# power.net
KiCad netlist of a schematic drawn in Altium Designer
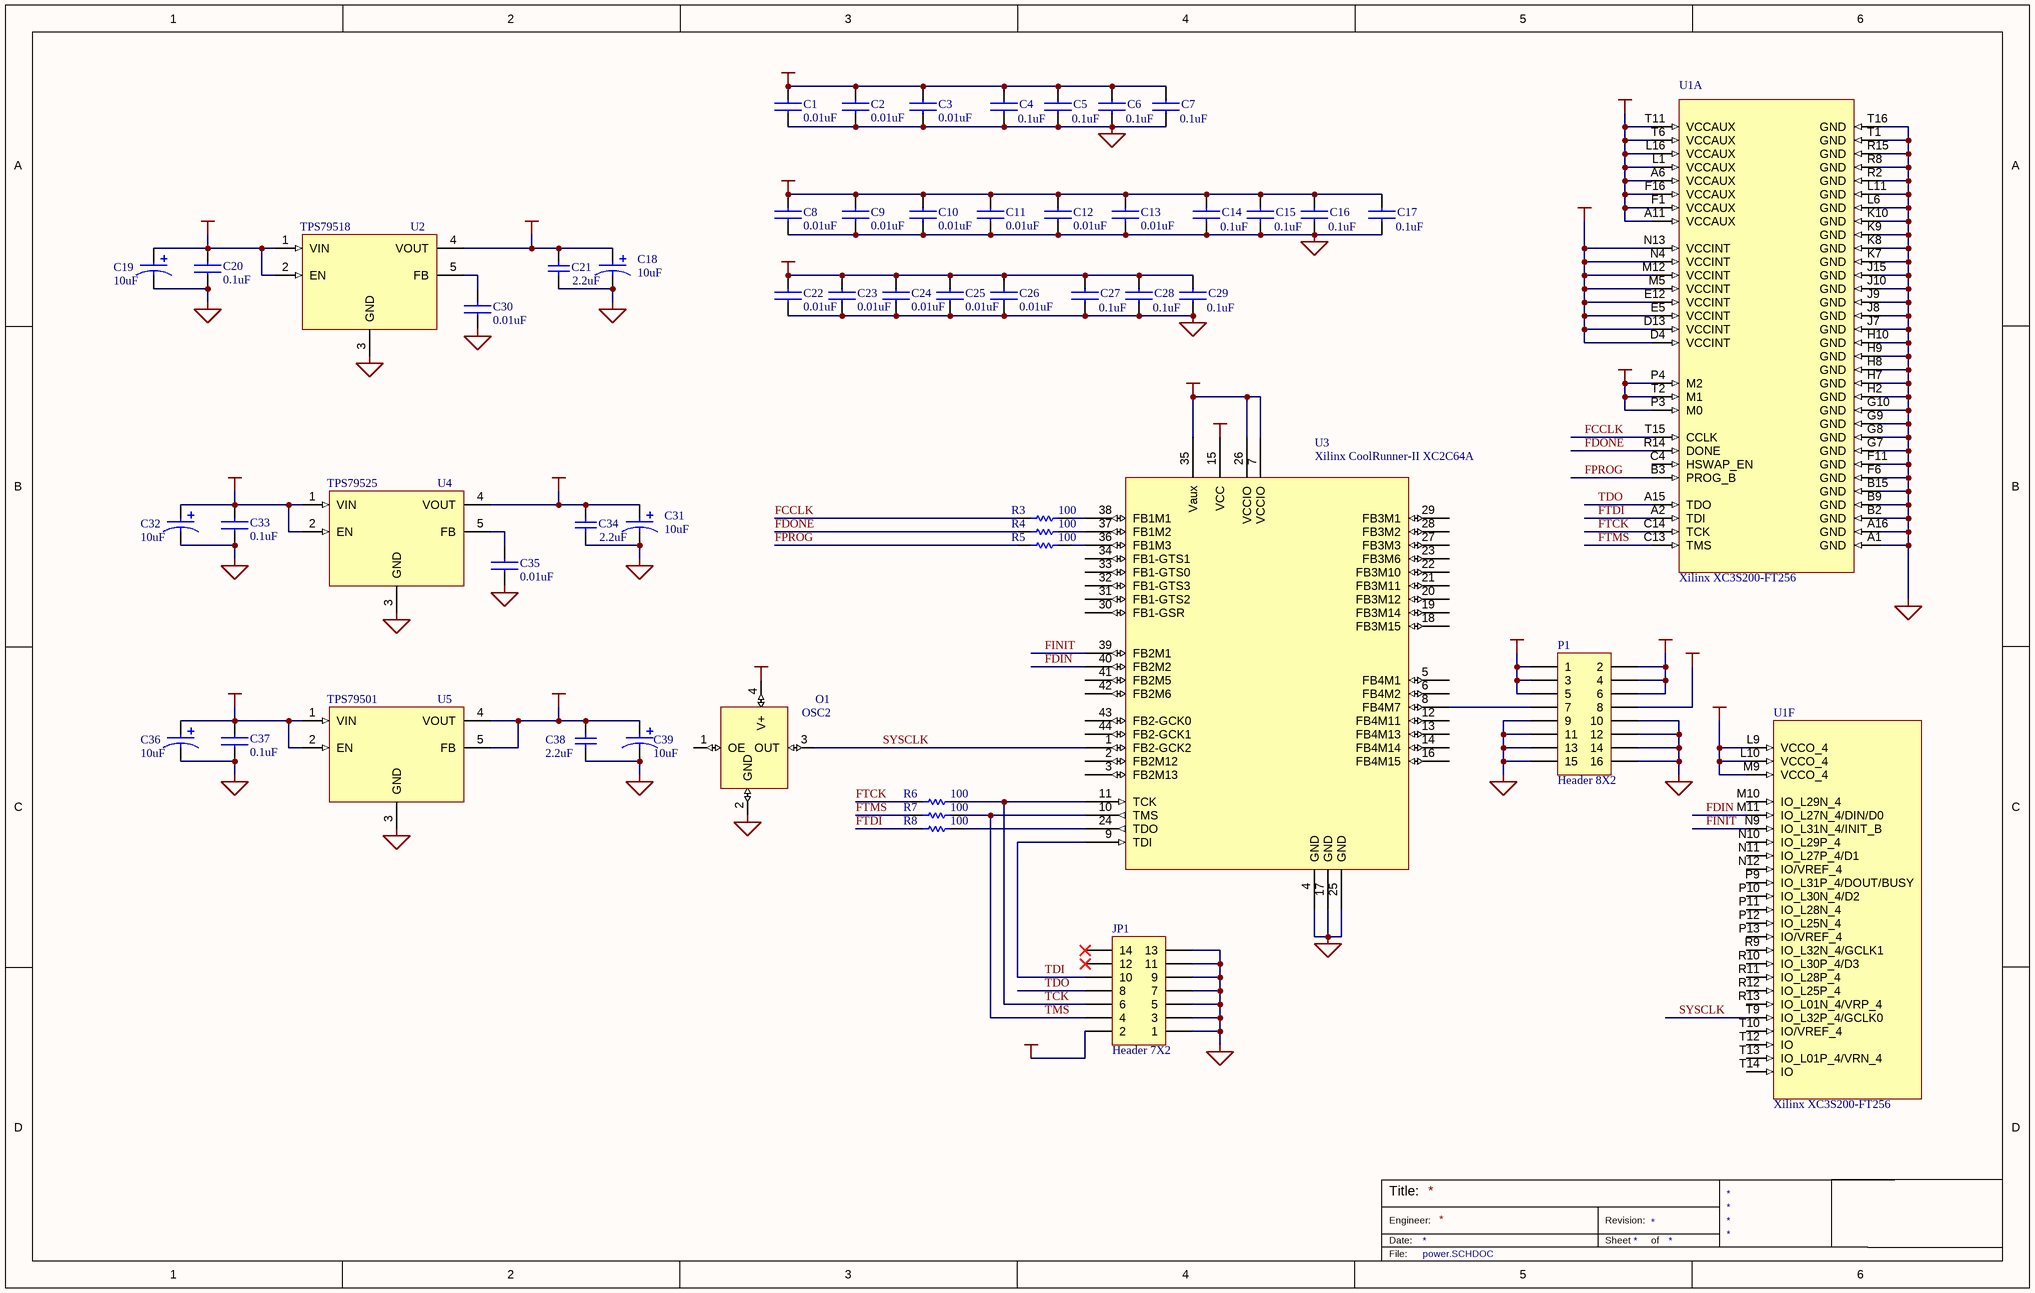
[diagram p0: power.SCHDOC]

(export (version "E")
  (design (tool "Eeschema 10.0.6"))
  (components
    (comp (ref "C1")
      (value "0.01uF")
      (footprint "0402")
      (description "Standard Capacitor")
      (fields (field (name "Comment") "CAPACITOR"))
      (libsource (lib "parts") (part "CAPACITOR"))
    )
    (comp (ref "C2")
      (value "0.01uF")
      (footprint "0402")
      (description "Standard Capacitor")
      (fields (field (name "Comment") "CAPACITOR"))
      (libsource (lib "parts") (part "CAPACITOR"))
    )
    (comp (ref "C3")
      (value "0.01uF")
      (footprint "0402")
      (description "Standard Capacitor")
      (fields (field (name "Comment") "CAPACITOR"))
      (libsource (lib "parts") (part "CAPACITOR"))
    )
    (comp (ref "C4")
      (value "0.1uF")
      (footprint "0603")
      (description "Standard Capacitor")
      (fields (field (name "Comment") "CAPACITOR"))
      (libsource (lib "parts") (part "CAPACITOR"))
    )
    (comp (ref "C5")
      (value "0.1uF")
      (footprint "0603")
      (description "Standard Capacitor")
      (fields (field (name "Comment") "CAPACITOR"))
      (libsource (lib "parts") (part "CAPACITOR"))
    )
    (comp (ref "C6")
      (value "0.1uF")
      (footprint "0603")
      (description "Standard Capacitor")
      (fields (field (name "Comment") "CAPACITOR"))
      (libsource (lib "parts") (part "CAPACITOR"))
    )
    (comp (ref "C7")
      (value "0.1uF")
      (footprint "0603")
      (description "Standard Capacitor")
      (fields (field (name "Comment") "CAPACITOR"))
      (libsource (lib "parts") (part "CAPACITOR"))
    )
    (comp (ref "C8")
      (value "0.01uF")
      (footprint "0402")
      (description "Standard Capacitor")
      (fields (field (name "Comment") "CAPACITOR"))
      (libsource (lib "parts") (part "CAPACITOR"))
    )
    (comp (ref "C9")
      (value "0.01uF")
      (footprint "0402")
      (description "Standard Capacitor")
      (fields (field (name "Comment") "CAPACITOR"))
      (libsource (lib "parts") (part "CAPACITOR"))
    )
    (comp (ref "C10")
      (value "0.01uF")
      (footprint "0402")
      (description "Standard Capacitor")
      (fields (field (name "Comment") "CAPACITOR"))
      (libsource (lib "parts") (part "CAPACITOR"))
    )
    (comp (ref "C11")
      (value "0.01uF")
      (footprint "0402")
      (description "Standard Capacitor")
      (fields (field (name "Comment") "CAPACITOR"))
      (libsource (lib "parts") (part "CAPACITOR"))
    )
    (comp (ref "C12")
      (value "0.01uF")
      (footprint "0402")
      (description "Standard Capacitor")
      (fields (field (name "Comment") "CAPACITOR"))
      (libsource (lib "parts") (part "CAPACITOR"))
    )
    (comp (ref "C13")
      (value "0.01uF")
      (footprint "0402")
      (description "Standard Capacitor")
      (fields (field (name "Comment") "CAPACITOR"))
      (libsource (lib "parts") (part "CAPACITOR"))
    )
    (comp (ref "C14")
      (value "0.1uF")
      (footprint "0603")
      (description "Standard Capacitor")
      (fields (field (name "Comment") "CAPACITOR"))
      (libsource (lib "parts") (part "CAPACITOR"))
    )
    (comp (ref "C15")
      (value "0.1uF")
      (footprint "0603")
      (description "Standard Capacitor")
      (fields (field (name "Comment") "CAPACITOR"))
      (libsource (lib "parts") (part "CAPACITOR"))
    )
    (comp (ref "C16")
      (value "0.1uF")
      (footprint "0603")
      (description "Standard Capacitor")
      (fields (field (name "Comment") "CAPACITOR"))
      (libsource (lib "parts") (part "CAPACITOR"))
    )
    (comp (ref "C17")
      (value "0.1uF")
      (footprint "0603")
      (description "Standard Capacitor")
      (fields (field (name "Comment") "CAPACITOR"))
      (libsource (lib "parts") (part "CAPACITOR"))
    )
    (comp (ref "C18")
      (value "10uF")
      (footprint "6032")
      (description "Standard Capacitor")
      (fields (field (name "Comment") "POLCAP2"))
      (libsource (lib "parts") (part "POLCAP2"))
    )
    (comp (ref "C19")
      (value "10uF")
      (footprint "6032")
      (description "Standard Capacitor")
      (fields (field (name "Comment") "POLCAP2"))
      (libsource (lib "parts") (part "POLCAP2"))
    )
    (comp (ref "C20")
      (value "0.1uF")
      (footprint "0603")
      (description "Standard Capacitor")
      (fields (field (name "Comment") "CAPACITOR"))
      (libsource (lib "parts") (part "CAPACITOR"))
    )
    (comp (ref "C21")
      (value "2.2uF")
      (footprint "1206")
      (description "Capacitor")
      (fields
        (field (name "MANUFACTURER") "Generic Components")
        (field (name "Comment") "Cap")
        (field (name "PUBLISHER") "Altium Limited")
      )
      (libsource (lib "Miscellaneous Devices") (part "Cap"))
    )
    (comp (ref "C22")
      (value "0.01uF")
      (footprint "0402")
      (description "Standard Capacitor")
      (fields (field (name "Comment") "CAPACITOR"))
      (libsource (lib "parts") (part "CAPACITOR"))
    )
    (comp (ref "C23")
      (value "0.01uF")
      (footprint "0402")
      (description "Standard Capacitor")
      (fields (field (name "Comment") "CAPACITOR"))
      (libsource (lib "parts") (part "CAPACITOR"))
    )
    (comp (ref "C24")
      (value "0.01uF")
      (footprint "0402")
      (description "Standard Capacitor")
      (fields (field (name "Comment") "CAPACITOR"))
      (libsource (lib "parts") (part "CAPACITOR"))
    )
    (comp (ref "C25")
      (value "0.01uF")
      (footprint "0402")
      (description "Standard Capacitor")
      (fields (field (name "Comment") "CAPACITOR"))
      (libsource (lib "parts") (part "CAPACITOR"))
    )
    (comp (ref "C26")
      (value "0.01uF")
      (footprint "0402")
      (description "Standard Capacitor")
      (fields (field (name "Comment") "CAPACITOR"))
      (libsource (lib "parts") (part "CAPACITOR"))
    )
    (comp (ref "C27")
      (value "0.1uF")
      (footprint "0603")
      (description "Standard Capacitor")
      (fields (field (name "Comment") "CAPACITOR"))
      (libsource (lib "parts") (part "CAPACITOR"))
    )
    (comp (ref "C28")
      (value "0.1uF")
      (footprint "0603")
      (description "Standard Capacitor")
      (fields (field (name "Comment") "CAPACITOR"))
      (libsource (lib "parts") (part "CAPACITOR"))
    )
    (comp (ref "C29")
      (value "0.1uF")
      (footprint "0603")
      (description "Standard Capacitor")
      (fields (field (name "Comment") "CAPACITOR"))
      (libsource (lib "parts") (part "CAPACITOR"))
    )
    (comp (ref "C30")
      (value "0.01uF")
      (footprint "0402")
      (description "Standard Capacitor")
      (fields (field (name "Comment") "CAPACITOR"))
      (libsource (lib "parts") (part "CAPACITOR"))
    )
    (comp (ref "C31")
      (value "10uF")
      (footprint "6032")
      (description "Standard Capacitor")
      (fields (field (name "Comment") "POLCAP2"))
      (libsource (lib "parts") (part "POLCAP2"))
    )
    (comp (ref "C32")
      (value "10uF")
      (footprint "6032")
      (description "Standard Capacitor")
      (fields (field (name "Comment") "POLCAP2"))
      (libsource (lib "parts") (part "POLCAP2"))
    )
    (comp (ref "C33")
      (value "0.1uF")
      (footprint "0603")
      (description "Standard Capacitor")
      (fields (field (name "Comment") "CAPACITOR"))
      (libsource (lib "parts") (part "CAPACITOR"))
    )
    (comp (ref "C34")
      (value "2.2uF")
      (footprint "1206")
      (description "Capacitor")
      (fields
        (field (name "MANUFACTURER") "Generic Components")
        (field (name "Comment") "Cap")
        (field (name "PUBLISHER") "Altium Limited")
      )
      (libsource (lib "Miscellaneous Devices") (part "Cap"))
    )
    (comp (ref "C35")
      (value "0.01uF")
      (footprint "0402")
      (description "Standard Capacitor")
      (fields (field (name "Comment") "CAPACITOR"))
      (libsource (lib "parts") (part "CAPACITOR"))
    )
    (comp (ref "C36")
      (value "10uF")
      (footprint "6032")
      (description "Standard Capacitor")
      (fields (field (name "Comment") "POLCAP2"))
      (libsource (lib "parts") (part "POLCAP2"))
    )
    (comp (ref "C37")
      (value "0.1uF")
      (footprint "0603")
      (description "Standard Capacitor")
      (fields (field (name "Comment") "CAPACITOR"))
      (libsource (lib "parts") (part "CAPACITOR"))
    )
    (comp (ref "C38")
      (value "2.2uF")
      (footprint "1206")
      (description "Capacitor")
      (fields
        (field (name "MANUFACTURER") "Generic Components")
        (field (name "Comment") "Cap")
        (field (name "PUBLISHER") "Altium Limited")
      )
      (libsource (lib "Miscellaneous Devices") (part "Cap"))
    )
    (comp (ref "C39")
      (value "10uF")
      (footprint "6032")
      (description "Standard Capacitor")
      (fields (field (name "Comment") "POLCAP2"))
      (libsource (lib "parts") (part "POLCAP2"))
    )
    (comp (ref "JP1")
      (value "Header 7X2")
      (footprint "SMT 2x7 2mm HDR")
      (description "Header, 7-Pin, Dual row")
      (fields (field (name "MANUFACTURER") "Generic Components") (field (name "PUBLISHER") "Altium Limited"))
      (libsource (lib "Miscellaneous Connectors") (part "Header 7X2"))
    )
    (comp (ref "O1")
      (value "OSC2")
      (footprint "ECS-3953M")
      (description "ECS SMD Oscillator, ECS-3953M")
      (libsource (lib "parts") (part "OSC2"))
    )
    (comp (ref "P1")
      (value "Header 8X2")
      (footprint "MOLEX 15-91-2160")
      (description "Header, 8-Pin, Dual row")
      (fields (field (name "PUBLISHER") "Altium Limited"))
      (libsource (lib "Miscellaneous Connectors") (part "Header 8X2"))
    )
    (comp (ref "R3")
      (value "100")
      (footprint "CC1608-0603")
      (description "Resistor")
      (fields
        (field (name "MANUFACTURER") "Generic Components")
        (field (name "TOLERANCE") "1%")
        (field (name "PUBLISHER") "Altium Limited")
      )
      (libsource (lib "Miscellaneous Devices") (part "Res1"))
    )
    (comp (ref "R4")
      (value "100")
      (footprint "CC1608-0603")
      (description "Resistor")
      (fields
        (field (name "MANUFACTURER") "Generic Components")
        (field (name "TOLERANCE") "1%")
        (field (name "PUBLISHER") "Altium Limited")
      )
      (libsource (lib "Miscellaneous Devices") (part "Res1"))
    )
    (comp (ref "R5")
      (value "100")
      (footprint "CC1608-0603")
      (description "Resistor")
      (fields
        (field (name "MANUFACTURER") "Generic Components")
        (field (name "TOLERANCE") "1%")
        (field (name "PUBLISHER") "Altium Limited")
      )
      (libsource (lib "Miscellaneous Devices") (part "Res1"))
    )
    (comp (ref "R6")
      (value "100")
      (footprint "CC1608-0603")
      (description "Resistor")
      (fields
        (field (name "MANUFACTURER") "Generic Components")
        (field (name "TOLERANCE") "1%")
        (field (name "PUBLISHER") "Altium Limited")
      )
      (libsource (lib "Miscellaneous Devices") (part "Res1"))
    )
    (comp (ref "R7")
      (value "100")
      (footprint "CC1608-0603")
      (description "Resistor")
      (fields
        (field (name "MANUFACTURER") "Generic Components")
        (field (name "TOLERANCE") "1%")
        (field (name "PUBLISHER") "Altium Limited")
      )
      (libsource (lib "Miscellaneous Devices") (part "Res1"))
    )
    (comp (ref "R8")
      (value "100")
      (footprint "CC1608-0603")
      (description "Resistor")
      (fields
        (field (name "MANUFACTURER") "Generic Components")
        (field (name "TOLERANCE") "1%")
        (field (name "PUBLISHER") "Altium Limited")
      )
      (libsource (lib "Miscellaneous Devices") (part "Res1"))
    )
    (comp (ref "U1")
      (value "Xilinx XC3S200-FT256")
      (footprint "Xilinx FT256 BGA")
      (description "Xilinx Spartan-3 FPGA")
      (libsource (lib "parts") (part "XC3S200-FT256"))
    )
    (comp (ref "U2")
      (value "TPS79518")
      (footprint "SOT223-5/Simple")
      (description "TI Ultra-low-noise LDO")
      (libsource (lib "parts") (part "TPS795XX"))
    )
    (comp (ref "U3")
      (value "Xilinx CoolRunner-II XC2C64A")
      (footprint "QFP10x10-G44/G10N")
      (libsource (lib "parts") (part "XC2C64A-5VQ44C"))
    )
    (comp (ref "U4")
      (value "TPS79525")
      (footprint "SOT223-5/Simple")
      (description "TI Ultra-low-noise LDO")
      (libsource (lib "parts") (part "TPS795XX"))
    )
    (comp (ref "U5")
      (value "TPS79501")
      (footprint "SOT223-5/Simple")
      (description "TI Ultra-low-noise LDO")
      (libsource (lib "parts") (part "TPS795XX"))
    )
  )
  (nets
    (net (code "1") (name "+1.2VCC") (class "Default")
      (node (ref "C1") (pin "1") (pintype "passive"))
      (node (ref "C2") (pin "1") (pintype "passive"))
      (node (ref "C3") (pin "1") (pintype "passive"))
      (node (ref "C38") (pin "2") (pinfunction "2_2") (pintype "passive"))
      (node (ref "C39") (pin "1") (pintype "passive"))
      (node (ref "C4") (pin "1") (pintype "passive"))
      (node (ref "C5") (pin "1") (pintype "passive"))
      (node (ref "C6") (pin "1") (pintype "passive"))
      (node (ref "C7") (pin "1") (pintype "passive"))
      (node (ref "U1") (pin "D13") (pinfunction "VCCINT_D13") (pintype "input"))
      (node (ref "U1") (pin "D4") (pinfunction "VCCINT_D4") (pintype "input"))
      (node (ref "U1") (pin "E12") (pinfunction "VCCINT_E12") (pintype "input"))
      (node (ref "U1") (pin "E5") (pinfunction "VCCINT_E5") (pintype "input"))
      (node (ref "U1") (pin "M12") (pinfunction "VCCINT_M12") (pintype "input"))
      (node (ref "U1") (pin "M5") (pinfunction "VCCINT_M5") (pintype "input"))
      (node (ref "U1") (pin "N13") (pinfunction "VCCINT_N13") (pintype "input"))
      (node (ref "U1") (pin "N4") (pinfunction "VCCINT_N4") (pintype "input"))
      (node (ref "U5") (pin "4") (pinfunction "VOUT_4") (pintype "power_in"))
      (node (ref "U5") (pin "5") (pinfunction "FB_5") (pintype "passive"))
    )
    (net (code "2") (name "+1.8VCC") (class "Default")
      (node (ref "C18") (pin "1") (pintype "passive"))
      (node (ref "C21") (pin "2") (pinfunction "2_2") (pintype "passive"))
      (node (ref "U2") (pin "4") (pinfunction "VOUT_4") (pintype "power_in"))
      (node (ref "U3") (pin "15") (pinfunction "VCC_15") (pintype "power_in"))
    )
    (net (code "3") (name "+2.5VCC") (class "Default")
      (node (ref "C10") (pin "1") (pintype "passive"))
      (node (ref "C11") (pin "1") (pintype "passive"))
      (node (ref "C12") (pin "1") (pintype "passive"))
      (node (ref "C13") (pin "1") (pintype "passive"))
      (node (ref "C14") (pin "1") (pintype "passive"))
      (node (ref "C15") (pin "1") (pintype "passive"))
      (node (ref "C16") (pin "1") (pintype "passive"))
      (node (ref "C17") (pin "1") (pintype "passive"))
      (node (ref "C31") (pin "1") (pintype "passive"))
      (node (ref "C34") (pin "2") (pinfunction "2_2") (pintype "passive"))
      (node (ref "C8") (pin "1") (pintype "passive"))
      (node (ref "C9") (pin "1") (pintype "passive"))
      (node (ref "U1") (pin "A11") (pinfunction "VCCAUX_A11") (pintype "input"))
      (node (ref "U1") (pin "A6") (pinfunction "VCCAUX_A6") (pintype "input"))
      (node (ref "U1") (pin "F1") (pinfunction "VCCAUX_F1") (pintype "input"))
      (node (ref "U1") (pin "F16") (pinfunction "VCCAUX_F16") (pintype "input"))
      (node (ref "U1") (pin "L1") (pinfunction "VCCAUX_L1") (pintype "input"))
      (node (ref "U1") (pin "L16") (pinfunction "VCCAUX_L16") (pintype "input"))
      (node (ref "U1") (pin "T11") (pinfunction "VCCAUX_T11") (pintype "input"))
      (node (ref "U1") (pin "T6") (pinfunction "VCCAUX_T6") (pintype "input"))
      (node (ref "U4") (pin "4") (pinfunction "VOUT_4") (pintype "power_in"))
    )
    (net (code "4") (name "+5VCC") (class "Default")
      (node (ref "P1") (pin "2") (pinfunction "2_2") (pintype "passive"))
      (node (ref "P1") (pin "4") (pinfunction "4_4") (pintype "passive"))
      (node (ref "P1") (pin "6") (pinfunction "6_6") (pintype "passive"))
    )
    (net (code "5") (name "+12VCC") (class "Default")
      (node (ref "P1") (pin "8") (pinfunction "8_8") (pintype "passive"))
    )
    (net (code "6") (name "/FCCLK") (class "Default")
      (node (ref "R3") (pin "2") (pinfunction "2_2") (pintype "passive"))
      (node (ref "U1") (pin "T15") (pinfunction "CCLK_T15") (pintype "input"))
    )
    (net (code "7") (name "/FDIN") (class "Default")
      (node (ref "U1") (pin "M11") (pinfunction "IO_L27N_4/DIN/D0_M11") (pintype "input"))
      (node (ref "U3") (pin "40") (pinfunction "FB2M2_40") (pintype "bidirectional"))
    )
    (net (code "8") (name "/FDONE") (class "Default")
      (node (ref "R4") (pin "2") (pinfunction "2_2") (pintype "passive"))
      (node (ref "U1") (pin "R14") (pinfunction "DONE_R14") (pintype "input"))
    )
    (net (code "9") (name "/FINIT") (class "Default")
      (node (ref "U1") (pin "N9") (pinfunction "IO_L31N_4/INIT_B_N9") (pintype "input"))
      (node (ref "U3") (pin "39") (pinfunction "FB2M1_39") (pintype "bidirectional"))
    )
    (net (code "10") (name "/FPROG") (class "Default")
      (node (ref "R5") (pin "2") (pinfunction "2_2") (pintype "passive"))
      (node (ref "U1") (pin "B3") (pinfunction "PROG_B_B3") (pintype "input"))
    )
    (net (code "11") (name "/FTCK") (class "Default")
      (node (ref "R6") (pin "2") (pinfunction "2_2") (pintype "passive"))
      (node (ref "U1") (pin "C14") (pinfunction "TCK_C14") (pintype "input"))
    )
    (net (code "12") (name "/FTDI") (class "Default")
      (node (ref "R8") (pin "2") (pinfunction "2_2") (pintype "passive"))
      (node (ref "U1") (pin "A2") (pinfunction "TDI_A2") (pintype "input"))
    )
    (net (code "13") (name "/FTMS") (class "Default")
      (node (ref "R7") (pin "1") (pinfunction "1_1") (pintype "passive"))
      (node (ref "U1") (pin "C13") (pinfunction "TMS_C13") (pintype "input"))
    )
    (net (code "14") (name "/SYSCLK") (class "Default")
      (node (ref "O1") (pin "3") (pinfunction "OUT_3") (pintype "bidirectional"))
      (node (ref "U1") (pin "T9") (pinfunction "IO_L32P_4/GCLK0_T9") (pintype "input"))
      (node (ref "U3") (pin "1") (pinfunction "FB2-GCK2_1") (pintype "bidirectional"))
    )
    (net (code "15") (name "/TCK") (class "Default")
      (node (ref "JP1") (pin "6") (pinfunction "6_6") (pintype "passive"))
      (node (ref "R6") (pin "1") (pinfunction "1_1") (pintype "passive"))
      (node (ref "U3") (pin "11") (pinfunction "TCK_11") (pintype "input"))
    )
    (net (code "16") (name "/TDI") (class "Default")
      (node (ref "JP1") (pin "10") (pinfunction "10_10") (pintype "passive"))
      (node (ref "U3") (pin "9") (pinfunction "TDI_9") (pintype "input"))
    )
    (net (code "17") (name "/TDO") (class "Default")
      (node (ref "JP1") (pin "8") (pinfunction "8_8") (pintype "passive"))
      (node (ref "U1") (pin "A15") (pinfunction "TDO_A15") (pintype "input"))
    )
    (net (code "18") (name "/TMS") (class "Default")
      (node (ref "JP1") (pin "4") (pinfunction "4_4") (pintype "passive"))
      (node (ref "R7") (pin "2") (pinfunction "2_2") (pintype "passive"))
      (node (ref "U3") (pin "10") (pinfunction "TMS_10") (pintype "output"))
    )
    (net (code "19") (name "GND") (class "Default")
      (node (ref "C1") (pin "2") (pintype "passive"))
      (node (ref "C10") (pin "2") (pintype "passive"))
      (node (ref "C11") (pin "2") (pintype "passive"))
      (node (ref "C12") (pin "2") (pintype "passive"))
      (node (ref "C13") (pin "2") (pintype "passive"))
      (node (ref "C14") (pin "2") (pintype "passive"))
      (node (ref "C15") (pin "2") (pintype "passive"))
      (node (ref "C16") (pin "2") (pintype "passive"))
      (node (ref "C17") (pin "2") (pintype "passive"))
      (node (ref "C18") (pin "2") (pintype "passive"))
      (node (ref "C19") (pin "2") (pintype "passive"))
      (node (ref "C2") (pin "2") (pintype "passive"))
      (node (ref "C20") (pin "1") (pintype "passive"))
      (node (ref "C21") (pin "1") (pinfunction "1_1") (pintype "passive"))
      (node (ref "C22") (pin "2") (pintype "passive"))
      (node (ref "C23") (pin "2") (pintype "passive"))
      (node (ref "C24") (pin "2") (pintype "passive"))
      (node (ref "C25") (pin "2") (pintype "passive"))
      (node (ref "C26") (pin "2") (pintype "passive"))
      (node (ref "C27") (pin "2") (pintype "passive"))
      (node (ref "C28") (pin "2") (pintype "passive"))
      (node (ref "C29") (pin "2") (pintype "passive"))
      (node (ref "C3") (pin "2") (pintype "passive"))
      (node (ref "C30") (pin "1") (pintype "passive"))
      (node (ref "C31") (pin "2") (pintype "passive"))
      (node (ref "C32") (pin "2") (pintype "passive"))
      (node (ref "C33") (pin "1") (pintype "passive"))
      (node (ref "C34") (pin "1") (pinfunction "1_1") (pintype "passive"))
      (node (ref "C35") (pin "1") (pintype "passive"))
      (node (ref "C36") (pin "2") (pintype "passive"))
      (node (ref "C37") (pin "1") (pintype "passive"))
      (node (ref "C38") (pin "1") (pinfunction "1_1") (pintype "passive"))
      (node (ref "C39") (pin "2") (pintype "passive"))
      (node (ref "C4") (pin "2") (pintype "passive"))
      (node (ref "C5") (pin "2") (pintype "passive"))
      (node (ref "C6") (pin "2") (pintype "passive"))
      (node (ref "C7") (pin "2") (pintype "passive"))
      (node (ref "C8") (pin "2") (pintype "passive"))
      (node (ref "C9") (pin "2") (pintype "passive"))
      (node (ref "JP1") (pin "1") (pinfunction "1_1") (pintype "passive"))
      (node (ref "JP1") (pin "11") (pinfunction "11_11") (pintype "passive"))
      (node (ref "JP1") (pin "13") (pinfunction "13_13") (pintype "passive"))
      (node (ref "JP1") (pin "3") (pinfunction "3_3") (pintype "passive"))
      (node (ref "JP1") (pin "5") (pinfunction "5_5") (pintype "passive"))
      (node (ref "JP1") (pin "7") (pinfunction "7_7") (pintype "passive"))
      (node (ref "JP1") (pin "9") (pinfunction "9_9") (pintype "passive"))
      (node (ref "O1") (pin "2") (pinfunction "GND_2") (pintype "bidirectional"))
      (node (ref "P1") (pin "10") (pinfunction "10_10") (pintype "passive"))
      (node (ref "P1") (pin "11") (pinfunction "11_11") (pintype "passive"))
      (node (ref "P1") (pin "12") (pinfunction "12_12") (pintype "passive"))
      (node (ref "P1") (pin "13") (pinfunction "13_13") (pintype "passive"))
      (node (ref "P1") (pin "14") (pinfunction "14_14") (pintype "passive"))
      (node (ref "P1") (pin "15") (pinfunction "15_15") (pintype "passive"))
      (node (ref "P1") (pin "16") (pinfunction "16_16") (pintype "passive"))
      (node (ref "P1") (pin "9") (pinfunction "9_9") (pintype "passive"))
      (node (ref "U1") (pin "A1") (pinfunction "GND_A1") (pintype "input"))
      (node (ref "U1") (pin "A16") (pinfunction "GND_A16") (pintype "input"))
      (node (ref "U1") (pin "B15") (pinfunction "GND_B15") (pintype "input"))
      (node (ref "U1") (pin "B2") (pinfunction "GND_B2") (pintype "input"))
      (node (ref "U1") (pin "B9") (pinfunction "GND_B9") (pintype "input"))
      (node (ref "U1") (pin "F11") (pinfunction "GND_F11") (pintype "input"))
      (node (ref "U1") (pin "F6") (pinfunction "GND_F6") (pintype "input"))
      (node (ref "U1") (pin "G10") (pinfunction "GND_G10") (pintype "input"))
      (node (ref "U1") (pin "G7") (pinfunction "GND_G7") (pintype "input"))
      (node (ref "U1") (pin "G8") (pinfunction "GND_G8") (pintype "input"))
      (node (ref "U1") (pin "G9") (pinfunction "GND_G9") (pintype "input"))
      (node (ref "U1") (pin "H10") (pinfunction "GND_H10") (pintype "input"))
      (node (ref "U1") (pin "H2") (pinfunction "GND_H2") (pintype "input"))
      (node (ref "U1") (pin "H7") (pinfunction "GND_H7") (pintype "input"))
      (node (ref "U1") (pin "H8") (pinfunction "GND_H8") (pintype "input"))
      (node (ref "U1") (pin "H9") (pinfunction "GND_H9") (pintype "input"))
      (node (ref "U1") (pin "J10") (pinfunction "GND_J10") (pintype "input"))
      (node (ref "U1") (pin "J15") (pinfunction "GND_J15") (pintype "input"))
      (node (ref "U1") (pin "J7") (pinfunction "GND_J7") (pintype "input"))
      (node (ref "U1") (pin "J8") (pinfunction "GND_J8") (pintype "input"))
      (node (ref "U1") (pin "J9") (pinfunction "GND_J9") (pintype "input"))
      (node (ref "U1") (pin "K10") (pinfunction "GND_K10") (pintype "input"))
      (node (ref "U1") (pin "K7") (pinfunction "GND_K7") (pintype "input"))
      (node (ref "U1") (pin "K8") (pinfunction "GND_K8") (pintype "input"))
      (node (ref "U1") (pin "K9") (pinfunction "GND_K9") (pintype "input"))
      (node (ref "U1") (pin "L11") (pinfunction "GND_L11") (pintype "input"))
      (node (ref "U1") (pin "L6") (pinfunction "GND_L6") (pintype "input"))
      (node (ref "U1") (pin "R15") (pinfunction "GND_R15") (pintype "input"))
      (node (ref "U1") (pin "R2") (pinfunction "GND_R2") (pintype "input"))
      (node (ref "U1") (pin "R8") (pinfunction "GND_R8") (pintype "input"))
      (node (ref "U1") (pin "T1") (pinfunction "GND_T1") (pintype "input"))
      (node (ref "U1") (pin "T16") (pinfunction "GND_T16") (pintype "input"))
      (node (ref "U2") (pin "3") (pinfunction "GND_3") (pintype "power_in"))
      (node (ref "U3") (pin "17") (pinfunction "GND_17") (pintype "power_in"))
      (node (ref "U3") (pin "25") (pinfunction "GND_25") (pintype "power_in"))
      (node (ref "U3") (pin "4") (pinfunction "GND_4") (pintype "power_in"))
      (node (ref "U4") (pin "3") (pinfunction "GND_3") (pintype "power_in"))
      (node (ref "U5") (pin "3") (pinfunction "GND_3") (pintype "power_in"))
    )
    (net (code "20") (name "Net-(U2-FB)") (class "Default")
      (node (ref "C30") (pin "2") (pintype "passive"))
      (node (ref "U2") (pin "5") (pinfunction "FB_5") (pintype "passive"))
    )
    (net (code "21") (name "Net-(U3-FB1M1)") (class "Default")
      (node (ref "R3") (pin "1") (pinfunction "1_1") (pintype "passive"))
      (node (ref "U3") (pin "38") (pinfunction "FB1M1_38") (pintype "bidirectional"))
    )
    (net (code "22") (name "Net-(U3-FB1M2)") (class "Default")
      (node (ref "R4") (pin "1") (pinfunction "1_1") (pintype "passive"))
      (node (ref "U3") (pin "37") (pinfunction "FB1M2_37") (pintype "bidirectional"))
    )
    (net (code "23") (name "Net-(U3-FB1M3)") (class "Default")
      (node (ref "R5") (pin "1") (pinfunction "1_1") (pintype "passive"))
      (node (ref "U3") (pin "36") (pinfunction "FB1M3_36") (pintype "bidirectional"))
    )
    (net (code "24") (name "Net-(U3-FB4M7)") (class "Default")
      (node (ref "P1") (pin "7") (pinfunction "7_7") (pintype "passive"))
      (node (ref "U3") (pin "8") (pinfunction "FB4M7_8") (pintype "bidirectional"))
    )
    (net (code "25") (name "Net-(U3-TDO)") (class "Default")
      (node (ref "R8") (pin "1") (pinfunction "1_1") (pintype "passive"))
      (node (ref "U3") (pin "24") (pinfunction "TDO_24") (pintype "output"))
    )
    (net (code "26") (name "Net-(U4-FB)") (class "Default")
      (node (ref "C35") (pin "2") (pintype "passive"))
      (node (ref "U4") (pin "5") (pinfunction "FB_5") (pintype "passive"))
    )
    (net (code "27") (name "VCC") (class "Default")
      (node (ref "C19") (pin "1") (pintype "passive"))
      (node (ref "C20") (pin "2") (pintype "passive"))
      (node (ref "C22") (pin "1") (pintype "passive"))
      (node (ref "C23") (pin "1") (pintype "passive"))
      (node (ref "C24") (pin "1") (pintype "passive"))
      (node (ref "C25") (pin "1") (pintype "passive"))
      (node (ref "C26") (pin "1") (pintype "passive"))
      (node (ref "C27") (pin "1") (pintype "passive"))
      (node (ref "C28") (pin "1") (pintype "passive"))
      (node (ref "C29") (pin "1") (pintype "passive"))
      (node (ref "C32") (pin "1") (pintype "passive"))
      (node (ref "C33") (pin "2") (pintype "passive"))
      (node (ref "C36") (pin "1") (pintype "passive"))
      (node (ref "C37") (pin "2") (pintype "passive"))
      (node (ref "JP1") (pin "2") (pinfunction "2_2") (pintype "passive"))
      (node (ref "O1") (pin "4") (pinfunction "V+_4") (pintype "bidirectional"))
      (node (ref "P1") (pin "1") (pinfunction "1_1") (pintype "passive"))
      (node (ref "P1") (pin "3") (pinfunction "3_3") (pintype "passive"))
      (node (ref "P1") (pin "5") (pinfunction "5_5") (pintype "passive"))
      (node (ref "U1") (pin "L10") (pinfunction "VCCO_4_L10") (pintype "input"))
      (node (ref "U1") (pin "L9") (pinfunction "VCCO_4_L9") (pintype "input"))
      (node (ref "U1") (pin "M9") (pinfunction "VCCO_4_M9") (pintype "input"))
      (node (ref "U1") (pin "P3") (pinfunction "M0_P3") (pintype "input"))
      (node (ref "U1") (pin "P4") (pinfunction "M2_P4") (pintype "input"))
      (node (ref "U1") (pin "T2") (pinfunction "M1_T2") (pintype "input"))
      (node (ref "U2") (pin "1") (pinfunction "VIN_1") (pintype "input"))
      (node (ref "U2") (pin "2") (pinfunction "EN_2") (pintype "input"))
      (node (ref "U3") (pin "26") (pinfunction "VCCIO_26") (pintype "power_in"))
      (node (ref "U3") (pin "35") (pinfunction "Vaux_35") (pintype "power_in"))
      (node (ref "U3") (pin "7") (pinfunction "VCCIO_7") (pintype "power_in"))
      (node (ref "U4") (pin "1") (pinfunction "VIN_1") (pintype "input"))
      (node (ref "U4") (pin "2") (pinfunction "EN_2") (pintype "input"))
      (node (ref "U5") (pin "1") (pinfunction "VIN_1") (pintype "input"))
      (node (ref "U5") (pin "2") (pinfunction "EN_2") (pintype "input"))
    )
    (net (code "28") (name "unconnected-(JP1-Pad12)") (class "Default")
      (node (ref "JP1") (pin "12") (pinfunction "12_12") (pintype "passive+no_connect"))
    )
    (net (code "29") (name "unconnected-(JP1-Pad14)") (class "Default")
      (node (ref "JP1") (pin "14") (pinfunction "14_14") (pintype "passive+no_connect"))
    )
    (net (code "30") (name "unconnected-(O1-OE-Pad1)") (class "Default")
      (node (ref "O1") (pin "1") (pinfunction "OE_1") (pintype "bidirectional"))
    )
    (net (code "31") (name "unconnected-(U1A-HSWAP_EN-PadC4)") (class "Default")
      (node (ref "U1") (pin "C4") (pinfunction "HSWAP_EN_C4") (pintype "input"))
    )
    (net (code "32") (name "unconnected-(U1F-IO-PadT12)") (class "Default")
      (node (ref "U1") (pin "T12") (pinfunction "IO_T12") (pintype "input"))
    )
    (net (code "33") (name "unconnected-(U1F-IO-PadT14)") (class "Default")
      (node (ref "U1") (pin "T14") (pinfunction "IO_T14") (pintype "input"))
    )
    (net (code "34") (name "unconnected-(U1F-IO_L01N_4{slash}VRP_4-PadR13)") (class "Default")
      (node (ref "U1") (pin "R13") (pinfunction "IO_L01N_4/VRP_4_R13") (pintype "input"))
    )
    (net (code "35") (name "unconnected-(U1F-IO_L01P_4{slash}VRN_4-PadT13)") (class "Default")
      (node (ref "U1") (pin "T13") (pinfunction "IO_L01P_4/VRN_4_T13") (pintype "input"))
    )
    (net (code "36") (name "unconnected-(U1F-IO_L25N_4-PadP12)") (class "Default")
      (node (ref "U1") (pin "P12") (pinfunction "IO_L25N_4_P12") (pintype "input"))
    )
    (net (code "37") (name "unconnected-(U1F-IO_L25P_4-PadR12)") (class "Default")
      (node (ref "U1") (pin "R12") (pinfunction "IO_L25P_4_R12") (pintype "input"))
    )
    (net (code "38") (name "unconnected-(U1F-IO_L27P_4{slash}D1-PadN11)") (class "Default")
      (node (ref "U1") (pin "N11") (pinfunction "IO_L27P_4/D1_N11") (pintype "input"))
    )
    (net (code "39") (name "unconnected-(U1F-IO_L28N_4-PadP11)") (class "Default")
      (node (ref "U1") (pin "P11") (pinfunction "IO_L28N_4_P11") (pintype "input"))
    )
    (net (code "40") (name "unconnected-(U1F-IO_L28P_4-PadR11)") (class "Default")
      (node (ref "U1") (pin "R11") (pinfunction "IO_L28P_4_R11") (pintype "input"))
    )
    (net (code "41") (name "unconnected-(U1F-IO_L29N_4-PadM10)") (class "Default")
      (node (ref "U1") (pin "M10") (pinfunction "IO_L29N_4_M10") (pintype "input"))
    )
    (net (code "42") (name "unconnected-(U1F-IO_L29P_4-PadN10)") (class "Default")
      (node (ref "U1") (pin "N10") (pinfunction "IO_L29P_4_N10") (pintype "input"))
    )
    (net (code "43") (name "unconnected-(U1F-IO_L30N_4{slash}D2-PadP10)") (class "Default")
      (node (ref "U1") (pin "P10") (pinfunction "IO_L30N_4/D2_P10") (pintype "input"))
    )
    (net (code "44") (name "unconnected-(U1F-IO_L30P_4{slash}D3-PadR10)") (class "Default")
      (node (ref "U1") (pin "R10") (pinfunction "IO_L30P_4/D3_R10") (pintype "input"))
    )
    (net (code "45") (name "unconnected-(U1F-IO_L31P_4{slash}DOUT{slash}BUSY-PadP9)") (class "Default")
      (node (ref "U1") (pin "P9") (pinfunction "IO_L31P_4/DOUT/BUSY_P9") (pintype "input"))
    )
    (net (code "46") (name "unconnected-(U1F-IO_L32N_4{slash}GCLK1-PadR9)") (class "Default")
      (node (ref "U1") (pin "R9") (pinfunction "IO_L32N_4/GCLK1_R9") (pintype "input"))
    )
    (net (code "47") (name "unconnected-(U1F-IO{slash}VREF_4-PadN12)") (class "Default")
      (node (ref "U1") (pin "N12") (pinfunction "IO/VREF_4_N12") (pintype "input"))
    )
    (net (code "48") (name "unconnected-(U1F-IO{slash}VREF_4-PadP13)") (class "Default")
      (node (ref "U1") (pin "P13") (pinfunction "IO/VREF_4_P13") (pintype "input"))
    )
    (net (code "49") (name "unconnected-(U1F-IO{slash}VREF_4-PadT10)") (class "Default")
      (node (ref "U1") (pin "T10") (pinfunction "IO/VREF_4_T10") (pintype "input"))
    )
    (net (code "50") (name "unconnected-(U3-FB1-GSR-Pad30)") (class "Default")
      (node (ref "U3") (pin "30") (pinfunction "FB1-GSR_30") (pintype "bidirectional"))
    )
    (net (code "51") (name "unconnected-(U3-FB1-GTS0-Pad33)") (class "Default")
      (node (ref "U3") (pin "33") (pinfunction "FB1-GTS0_33") (pintype "bidirectional"))
    )
    (net (code "52") (name "unconnected-(U3-FB1-GTS1-Pad34)") (class "Default")
      (node (ref "U3") (pin "34") (pinfunction "FB1-GTS1_34") (pintype "bidirectional"))
    )
    (net (code "53") (name "unconnected-(U3-FB1-GTS2-Pad31)") (class "Default")
      (node (ref "U3") (pin "31") (pinfunction "FB1-GTS2_31") (pintype "bidirectional"))
    )
    (net (code "54") (name "unconnected-(U3-FB1-GTS3-Pad32)") (class "Default")
      (node (ref "U3") (pin "32") (pinfunction "FB1-GTS3_32") (pintype "bidirectional"))
    )
    (net (code "55") (name "unconnected-(U3-FB2-GCK0-Pad43)") (class "Default")
      (node (ref "U3") (pin "43") (pinfunction "FB2-GCK0_43") (pintype "bidirectional"))
    )
    (net (code "56") (name "unconnected-(U3-FB2-GCK1-Pad44)") (class "Default")
      (node (ref "U3") (pin "44") (pinfunction "FB2-GCK1_44") (pintype "bidirectional"))
    )
    (net (code "57") (name "unconnected-(U3-FB2M5-Pad41)") (class "Default")
      (node (ref "U3") (pin "41") (pinfunction "FB2M5_41") (pintype "bidirectional"))
    )
    (net (code "58") (name "unconnected-(U3-FB2M6-Pad42)") (class "Default")
      (node (ref "U3") (pin "42") (pinfunction "FB2M6_42") (pintype "bidirectional"))
    )
    (net (code "59") (name "unconnected-(U3-FB2M12-Pad2)") (class "Default")
      (node (ref "U3") (pin "2") (pinfunction "FB2M12_2") (pintype "bidirectional"))
    )
    (net (code "60") (name "unconnected-(U3-FB2M13-Pad3)") (class "Default")
      (node (ref "U3") (pin "3") (pinfunction "FB2M13_3") (pintype "bidirectional"))
    )
    (net (code "61") (name "unconnected-(U3-FB3M1-Pad29)") (class "Default")
      (node (ref "U3") (pin "29") (pinfunction "FB3M1_29") (pintype "bidirectional"))
    )
    (net (code "62") (name "unconnected-(U3-FB3M2-Pad28)") (class "Default")
      (node (ref "U3") (pin "28") (pinfunction "FB3M2_28") (pintype "bidirectional"))
    )
    (net (code "63") (name "unconnected-(U3-FB3M3-Pad27)") (class "Default")
      (node (ref "U3") (pin "27") (pinfunction "FB3M3_27") (pintype "bidirectional"))
    )
    (net (code "64") (name "unconnected-(U3-FB3M6-Pad23)") (class "Default")
      (node (ref "U3") (pin "23") (pinfunction "FB3M6_23") (pintype "bidirectional"))
    )
    (net (code "65") (name "unconnected-(U3-FB3M10-Pad22)") (class "Default")
      (node (ref "U3") (pin "22") (pinfunction "FB3M10_22") (pintype "bidirectional"))
    )
    (net (code "66") (name "unconnected-(U3-FB3M11-Pad21)") (class "Default")
      (node (ref "U3") (pin "21") (pinfunction "FB3M11_21") (pintype "bidirectional"))
    )
    (net (code "67") (name "unconnected-(U3-FB3M12-Pad20)") (class "Default")
      (node (ref "U3") (pin "20") (pinfunction "FB3M12_20") (pintype "bidirectional"))
    )
    (net (code "68") (name "unconnected-(U3-FB3M14-Pad19)") (class "Default")
      (node (ref "U3") (pin "19") (pinfunction "FB3M14_19") (pintype "bidirectional"))
    )
    (net (code "69") (name "unconnected-(U3-FB3M15-Pad18)") (class "Default")
      (node (ref "U3") (pin "18") (pinfunction "FB3M15_18") (pintype "bidirectional"))
    )
    (net (code "70") (name "unconnected-(U3-FB4M1-Pad5)") (class "Default")
      (node (ref "U3") (pin "5") (pinfunction "FB4M1_5") (pintype "bidirectional"))
    )
    (net (code "71") (name "unconnected-(U3-FB4M2-Pad6)") (class "Default")
      (node (ref "U3") (pin "6") (pinfunction "FB4M2_6") (pintype "bidirectional"))
    )
    (net (code "72") (name "unconnected-(U3-FB4M11-Pad12)") (class "Default")
      (node (ref "U3") (pin "12") (pinfunction "FB4M11_12") (pintype "bidirectional"))
    )
    (net (code "73") (name "unconnected-(U3-FB4M13-Pad13)") (class "Default")
      (node (ref "U3") (pin "13") (pinfunction "FB4M13_13") (pintype "bidirectional"))
    )
    (net (code "74") (name "unconnected-(U3-FB4M14-Pad14)") (class "Default")
      (node (ref "U3") (pin "14") (pinfunction "FB4M14_14") (pintype "bidirectional"))
    )
    (net (code "75") (name "unconnected-(U3-FB4M15-Pad16)") (class "Default")
      (node (ref "U3") (pin "16") (pinfunction "FB4M15_16") (pintype "bidirectional"))
    )
  )
)
